# MCU023_MSP432E_GPIO_USB.net
KiCad netlist of a schematic drawn in Altium Designer
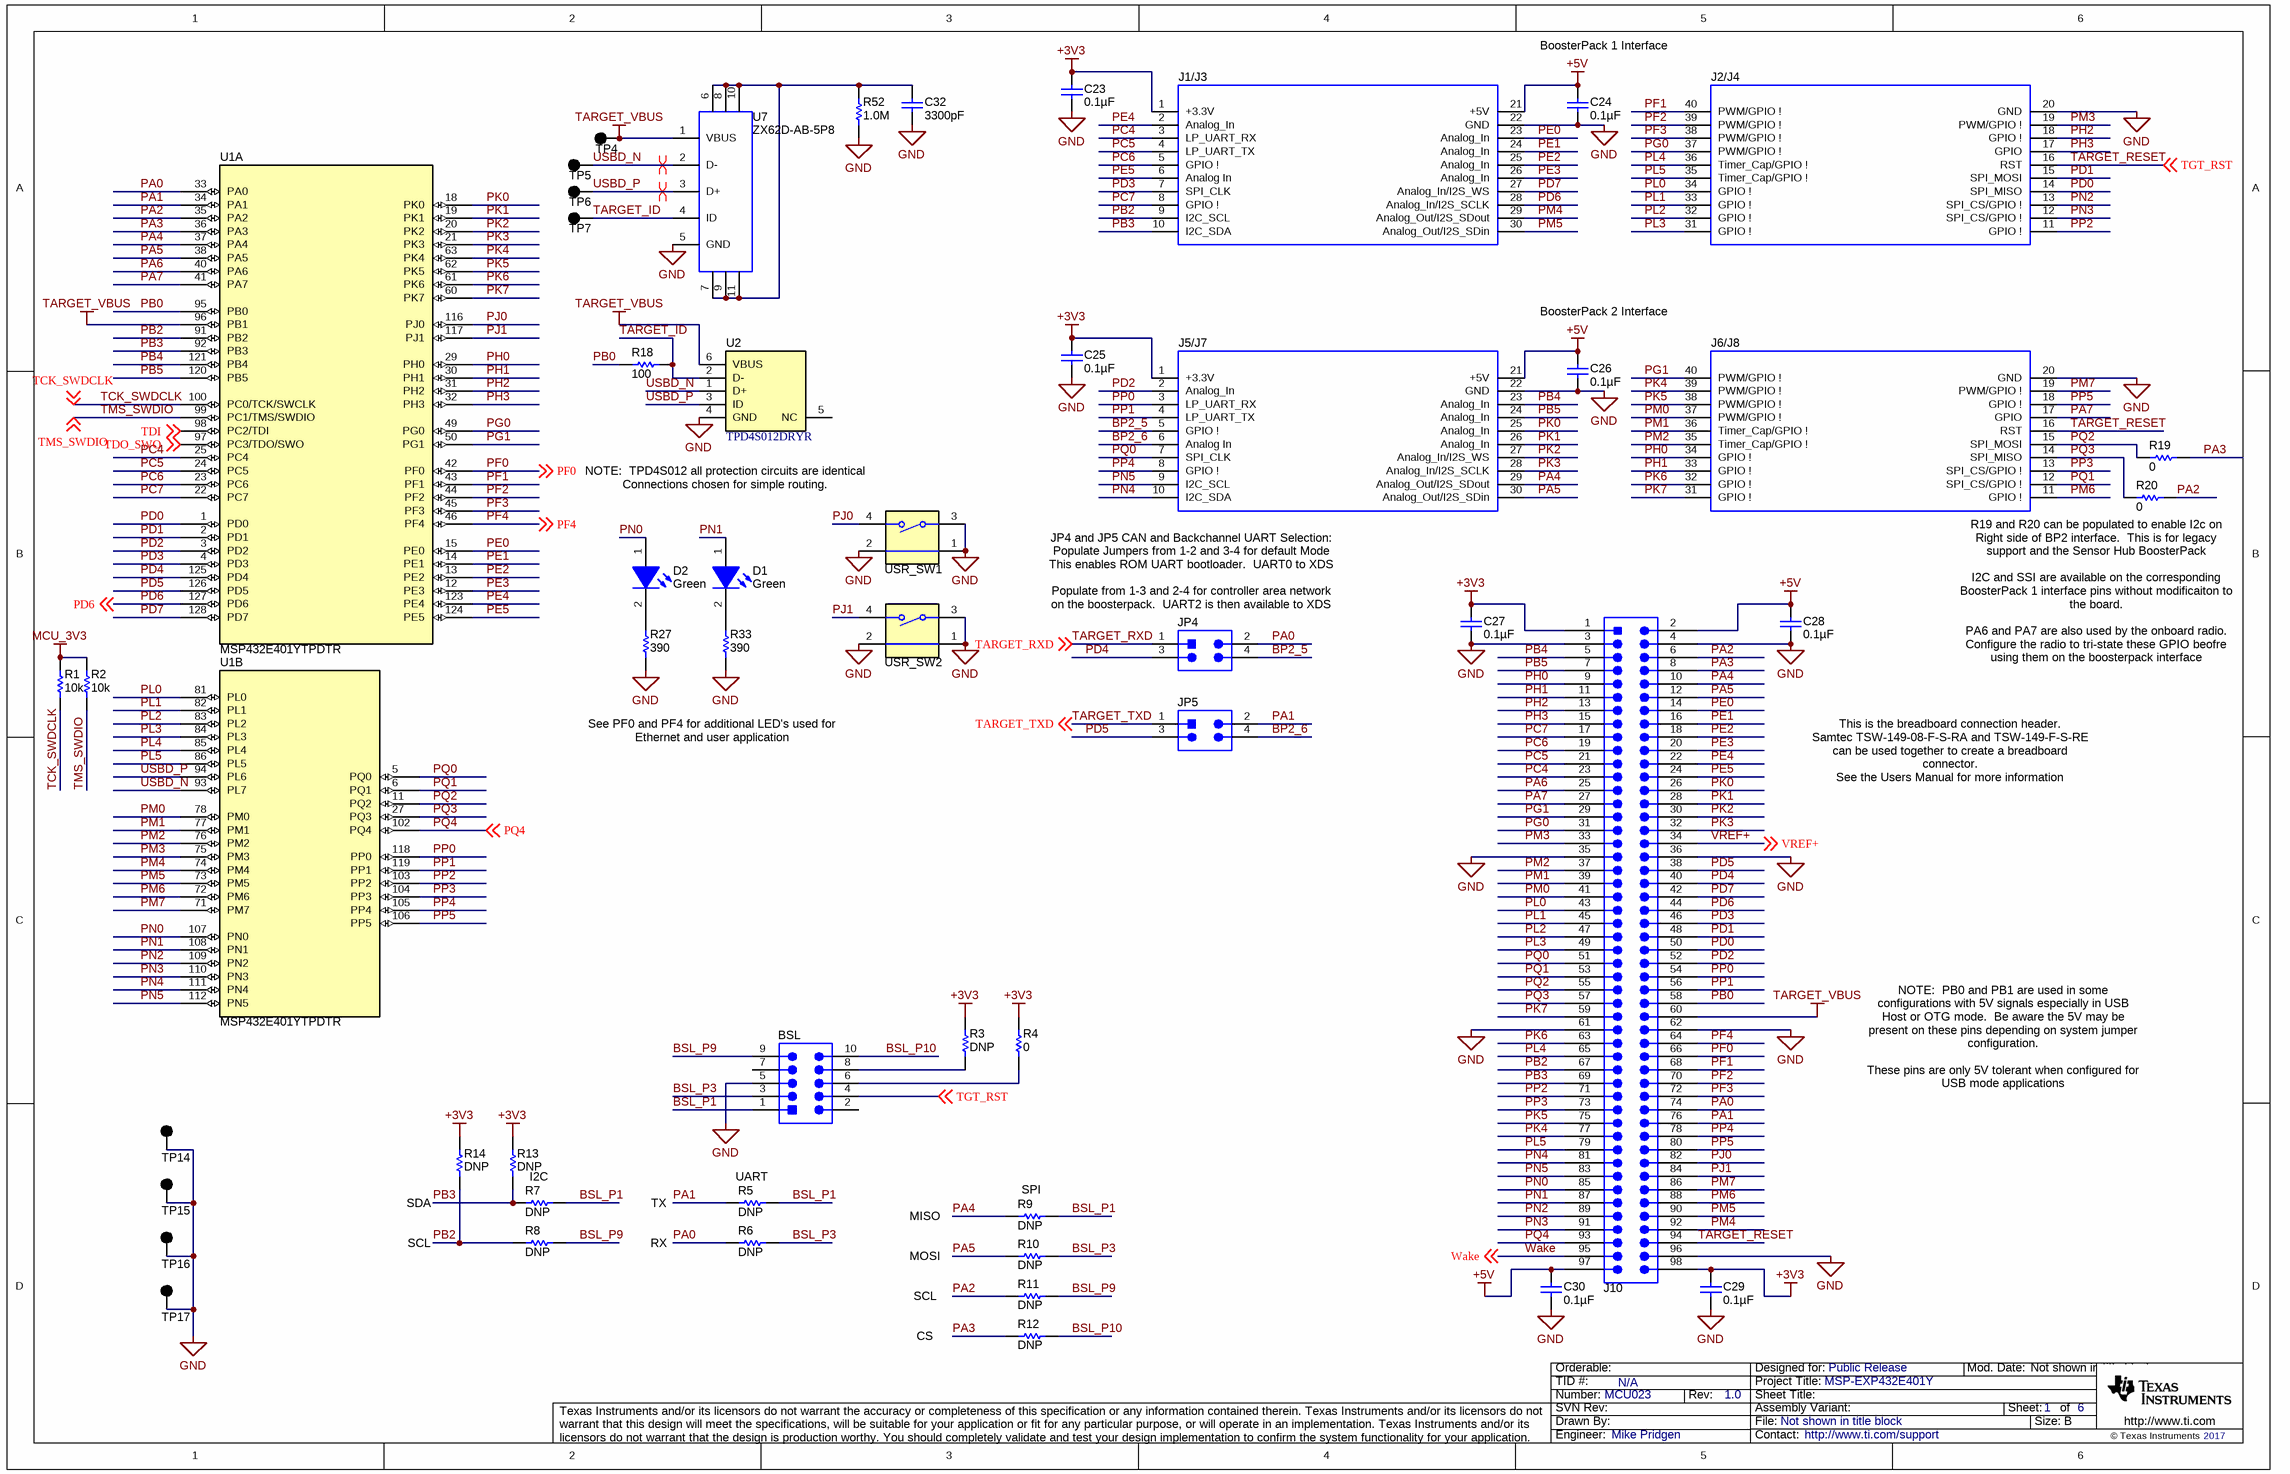
[diagram p0: MCU023_MSP432E_GPIO_USB.SchDoc]

(export (version "E")
  (design (tool "Eeschema 10.0.6"))
  (components
    (comp (ref "BSL")
      (value "AWHW-10G-0202-T")
      (footprint "Assman_AWHW-10G-0x02-T")
      (description "Header(Shrouded), 2.54mm, 5x2, Gold, TH")
      (fields
        (field (name "MANUFACTURER") "Assman WSW")
        (field (name "SYMBOLCREATOR") "a0412235")
        (field (name "PUBLISHER") "Texas Instruments")
      )
      (libsource (lib "Connectors_Other") (part "AWHW-10G-0202-T"))
    )
    (comp (ref "C23")
      (value "GRM155R71C104KA88D")
      (footprint "0402")
      (description "CAP, CERM, 0.1 µF, 16 V, +/- 10%, X7R, 0402")
      (fields
        (field (name "VALUEDISPLAYED") "0.1µF")
        (field (name "MANUFACTURER") "MuRata")
        (field (name "PUBLISHER") "Texas Instruments")
      )
      (libsource (lib "Capacitor_Ceramic") (part "GRM155R71C104KA88D"))
    )
    (comp (ref "C24")
      (value "GRM155R71C104KA88D")
      (footprint "0402")
      (description "CAP, CERM, 0.1 µF, 16 V, +/- 10%, X7R, 0402")
      (fields
        (field (name "VALUEDISPLAYED") "0.1µF")
        (field (name "MANUFACTURER") "MuRata")
        (field (name "PUBLISHER") "Texas Instruments")
      )
      (libsource (lib "Capacitor_Ceramic") (part "GRM155R71C104KA88D"))
    )
    (comp (ref "C25")
      (value "GRM155R71C104KA88D")
      (footprint "0402")
      (description "CAP, CERM, 0.1 µF, 16 V, +/- 10%, X7R, 0402")
      (fields
        (field (name "VALUEDISPLAYED") "0.1µF")
        (field (name "MANUFACTURER") "MuRata")
        (field (name "PUBLISHER") "Texas Instruments")
      )
      (libsource (lib "Capacitor_Ceramic") (part "GRM155R71C104KA88D"))
    )
    (comp (ref "C26")
      (value "GRM155R71C104KA88D")
      (footprint "0402")
      (description "CAP, CERM, 0.1 µF, 16 V, +/- 10%, X7R, 0402")
      (fields
        (field (name "VALUEDISPLAYED") "0.1µF")
        (field (name "MANUFACTURER") "MuRata")
        (field (name "PUBLISHER") "Texas Instruments")
      )
      (libsource (lib "Capacitor_Ceramic") (part "GRM155R71C104KA88D"))
    )
    (comp (ref "C27")
      (value "GRM155R71C104KA88D")
      (footprint "0402")
      (description "CAP, CERM, 0.1 µF, 16 V, +/- 10%, X7R, 0402")
      (fields
        (field (name "VALUEDISPLAYED") "0.1µF")
        (field (name "MANUFACTURER") "MuRata")
        (field (name "PUBLISHER") "Texas Instruments")
      )
      (libsource (lib "Capacitor_Ceramic") (part "GRM155R71C104KA88D"))
    )
    (comp (ref "C28")
      (value "GRM155R71C104KA88D")
      (footprint "0402")
      (description "CAP, CERM, 0.1 µF, 16 V, +/- 10%, X7R, 0402")
      (fields
        (field (name "VALUEDISPLAYED") "0.1µF")
        (field (name "MANUFACTURER") "MuRata")
        (field (name "PUBLISHER") "Texas Instruments")
      )
      (libsource (lib "Capacitor_Ceramic") (part "GRM155R71C104KA88D"))
    )
    (comp (ref "C29")
      (value "GRM155R71C104KA88D")
      (footprint "0402")
      (description "CAP, CERM, 0.1 µF, 16 V, +/- 10%, X7R, 0402")
      (fields
        (field (name "VALUEDISPLAYED") "0.1µF")
        (field (name "MANUFACTURER") "MuRata")
        (field (name "PUBLISHER") "Texas Instruments")
      )
      (libsource (lib "Capacitor_Ceramic") (part "GRM155R71C104KA88D"))
    )
    (comp (ref "C30")
      (value "GRM155R71C104KA88D")
      (footprint "0402")
      (description "CAP, CERM, 0.1 µF, 16 V, +/- 10%, X7R, 0402")
      (fields
        (field (name "VALUEDISPLAYED") "0.1µF")
        (field (name "MANUFACTURER") "MuRata")
        (field (name "PUBLISHER") "Texas Instruments")
      )
      (libsource (lib "Capacitor_Ceramic") (part "GRM155R71C104KA88D"))
    )
    (comp (ref "C32")
      (value "GRM188R71H332KA01D")
      (footprint "0603")
      (description "CAP, CERM, 3300 pF, 50 V, +/- 10%, X7R, 0603")
      (fields
        (field (name "VALUEDISPLAYED") "3300pF")
        (field (name "MANUFACTURER") "MuRata")
        (field (name "PUBLISHER") "Texas Instruments")
      )
      (libsource (lib "Capacitor_Ceramic") (part "GRM188R71H332KA01D"))
    )
    (comp (ref "D1")
      (value "Green")
      (footprint "LED_LTST-C190")
      (description "LED, Green, SMD")
      (fields
        (field (name "PARTNUMBER") "LTST-C190GKT")
        (field (name "MANUFACTURER") "Lite-On")
        (field (name "PUBLISHER") "Texas Instruments")
      )
      (libsource (lib "LED") (part "LTST-C190GKT"))
    )
    (comp (ref "D2")
      (value "Green")
      (footprint "LED_LTST-C190")
      (description "LED, Green, SMD")
      (fields
        (field (name "PARTNUMBER") "LTST-C190GKT")
        (field (name "MANUFACTURER") "Lite-On")
        (field (name "PUBLISHER") "Texas Instruments")
      )
      (libsource (lib "LED") (part "LTST-C190GKT"))
    )
    (comp (ref "J1/J3")
      (value "SSQ-110-03-T-D")
      (footprint "BoosterPack_40pin_J1J3")
      (description "Receptacle, 2.54mm, 10x2, Tin, TH")
      (fields
        (field (name "MANUFACTURER") "Samtec")
        (field (name "ALTERNATE PARTNUMBER") "CRD-081413-A-G")
        (field (name "SYMBOLCREATOR") "a0412235")
        (field (name "PUBLISHER") "Texas Instruments")
      )
      (libsource (lib "Hardware") (part "BoosterPack_40pin_J1J3"))
    )
    (comp (ref "J2/J4")
      (value "SSQ-110-03-T-D")
      (footprint "BoosterPack_40pin_J2J4")
      (description "Receptacle, 2.54mm, 10x2, Tin, TH")
      (fields
        (field (name "MANUFACTURER") "Samtec")
        (field (name "ALTERNATE PARTNUMBER") "CRD-081413-A-G")
        (field (name "SYMBOLCREATOR") "a0412235")
        (field (name "PUBLISHER") "Texas Instruments")
      )
      (libsource (lib "Hardware") (part "BoosterPack_40pin_J2J4"))
    )
    (comp (ref "J5/J7")
      (value "SSQ-110-03-T-D")
      (footprint "BoosterPack_40pin_J1J3")
      (description "Receptacle, 2.54mm, 10x2, Tin, TH")
      (fields
        (field (name "MANUFACTURER") "Samtec")
        (field (name "ALTERNATE PARTNUMBER") "CRD-081413-A-G")
        (field (name "SYMBOLCREATOR") "a0412235")
        (field (name "PUBLISHER") "Texas Instruments")
      )
      (libsource (lib "Hardware") (part "BoosterPack_40pin_J1J3"))
    )
    (comp (ref "J6/J8")
      (value "SSQ-110-03-T-D")
      (footprint "BoosterPack_40pin_J2J4")
      (description "Receptacle, 2.54mm, 10x2, Tin, TH")
      (fields
        (field (name "MANUFACTURER") "Samtec")
        (field (name "ALTERNATE PARTNUMBER") "CRD-081413-A-G")
        (field (name "SYMBOLCREATOR") "a0412235")
        (field (name "PUBLISHER") "Texas Instruments")
      )
      (libsource (lib "Hardware") (part "BoosterPack_40pin_J2J4"))
    )
    (comp (ref "J10")
      (value "TSW-149-07-S-D")
      (footprint "Samtec_TSW-149-07-x-D")
      (description "Header, 2.54mm, 49x2, Gold, TH")
      (fields
        (field (name "MANUFACTURER") "Samtec")
        (field (name "SYMBOLCREATOR") "Altium")
        (field (name "PUBLISHER") "Texas Instruments")
      )
      (libsource (lib "Connectors_Samtec1") (part "TSW-149-07-S-D"))
    )
    (comp (ref "JP4")
      (value "PBC02DAAN")
      (footprint "Sullins_PxC02DAAN")
      (description "Header, 2.54mm, 2x2, Gold, TH")
      (fields
        (field (name "MANUFACTURER") "Sullins Connector Solutions")
        (field (name "SYMBOLCREATOR") "a0412235")
        (field (name "PUBLISHER") "Texas Instruments")
      )
      (libsource (lib "Connectors_Sullins") (part "PBC02DAAN"))
    )
    (comp (ref "JP5")
      (value "PBC02DAAN")
      (footprint "Sullins_PxC02DAAN")
      (description "Header, 2.54mm, 2x2, Gold, TH")
      (fields
        (field (name "MANUFACTURER") "Sullins Connector Solutions")
        (field (name "SYMBOLCREATOR") "a0412235")
        (field (name "PUBLISHER") "Texas Instruments")
      )
      (libsource (lib "Connectors_Sullins") (part "PBC02DAAN"))
    )
    (comp (ref "R1")
      (value "CRCW040210K0JNED")
      (footprint "0402")
      (description "RES, 10 k, 5%, 0.063 W, 0402")
      (fields
        (field (name "VALUEDISPLAYED") "10k")
        (field (name "MANUFACTURER") "Vishay-Dale")
        (field (name "PUBLISHER") "Texas Instruments")
      )
      (libsource (lib "Resistor_0402") (part "CRCW040210K0JNED"))
    )
    (comp (ref "R2")
      (value "CRCW040210K0JNED")
      (footprint "0402")
      (description "RES, 10 k, 5%, 0.063 W, 0402")
      (fields
        (field (name "VALUEDISPLAYED") "10k")
        (field (name "MANUFACTURER") "Vishay-Dale")
        (field (name "PUBLISHER") "Texas Instruments")
      )
      (libsource (lib "Resistor_0402") (part "CRCW040210K0JNED"))
    )
    (comp (ref "R3")
      (value "ERJ-2GE0R00X")
      (footprint "0402")
      (description "RES, 0, 5%, 0.063 W, 0402")
      (fields
        (field (name "VALUEDISPLAYED") "DNP")
        (field (name "MANUFACTURER") "Panasonic")
        (field (name "PUBLISHER") "Texas Instruments")
      )
      (libsource (lib "Resistor_0402") (part "ERJ-2GE0R00X"))
    )
    (comp (ref "R4")
      (value "ERJ-2GE0R00X")
      (footprint "0402")
      (description "RES, 0, 5%, 0.063 W, 0402")
      (fields
        (field (name "VALUEDISPLAYED") "0")
        (field (name "MANUFACTURER") "Panasonic")
        (field (name "PUBLISHER") "Texas Instruments")
      )
      (libsource (lib "Resistor_0402") (part "ERJ-2GE0R00X"))
    )
    (comp (ref "R5")
      (value "ERJ-2GE0R00X")
      (footprint "0402")
      (description "RES, 0, 5%, 0.063 W, 0402")
      (fields
        (field (name "VALUEDISPLAYED") "DNP")
        (field (name "MANUFACTURER") "Panasonic")
        (field (name "PUBLISHER") "Texas Instruments")
      )
      (libsource (lib "Resistor_0402") (part "ERJ-2GE0R00X"))
    )
    (comp (ref "R6")
      (value "ERJ-2GE0R00X")
      (footprint "0402")
      (description "RES, 0, 5%, 0.063 W, 0402")
      (fields
        (field (name "VALUEDISPLAYED") "DNP")
        (field (name "MANUFACTURER") "Panasonic")
        (field (name "PUBLISHER") "Texas Instruments")
      )
      (libsource (lib "Resistor_0402") (part "ERJ-2GE0R00X"))
    )
    (comp (ref "R7")
      (value "ERJ-2GE0R00X")
      (footprint "0402")
      (description "RES, 0, 5%, 0.063 W, 0402")
      (fields
        (field (name "VALUEDISPLAYED") "DNP")
        (field (name "MANUFACTURER") "Panasonic")
        (field (name "PUBLISHER") "Texas Instruments")
      )
      (libsource (lib "Resistor_0402") (part "ERJ-2GE0R00X"))
    )
    (comp (ref "R8")
      (value "ERJ-2GE0R00X")
      (footprint "0402")
      (description "RES, 0, 5%, 0.063 W, 0402")
      (fields
        (field (name "VALUEDISPLAYED") "DNP")
        (field (name "MANUFACTURER") "Panasonic")
        (field (name "PUBLISHER") "Texas Instruments")
      )
      (libsource (lib "Resistor_0402") (part "ERJ-2GE0R00X"))
    )
    (comp (ref "R9")
      (value "ERJ-2GE0R00X")
      (footprint "0402")
      (description "RES, 0, 5%, 0.063 W, 0402")
      (fields
        (field (name "VALUEDISPLAYED") "DNP")
        (field (name "MANUFACTURER") "Panasonic")
        (field (name "PUBLISHER") "Texas Instruments")
      )
      (libsource (lib "Resistor_0402") (part "ERJ-2GE0R00X"))
    )
    (comp (ref "R10")
      (value "ERJ-2GE0R00X")
      (footprint "0402")
      (description "RES, 0, 5%, 0.063 W, 0402")
      (fields
        (field (name "VALUEDISPLAYED") "DNP")
        (field (name "MANUFACTURER") "Panasonic")
        (field (name "PUBLISHER") "Texas Instruments")
      )
      (libsource (lib "Resistor_0402") (part "ERJ-2GE0R00X"))
    )
    (comp (ref "R11")
      (value "ERJ-2GE0R00X")
      (footprint "0402")
      (description "RES, 0, 5%, 0.063 W, 0402")
      (fields
        (field (name "VALUEDISPLAYED") "DNP")
        (field (name "MANUFACTURER") "Panasonic")
        (field (name "PUBLISHER") "Texas Instruments")
      )
      (libsource (lib "Resistor_0402") (part "ERJ-2GE0R00X"))
    )
    (comp (ref "R12")
      (value "ERJ-2GE0R00X")
      (footprint "0402")
      (description "RES, 0, 5%, 0.063 W, 0402")
      (fields
        (field (name "VALUEDISPLAYED") "DNP")
        (field (name "MANUFACTURER") "Panasonic")
        (field (name "PUBLISHER") "Texas Instruments")
      )
      (libsource (lib "Resistor_0402") (part "ERJ-2GE0R00X"))
    )
    (comp (ref "R13")
      (value "CRCW04023K30JNED")
      (footprint "0402")
      (description "RES, 3.3 k, 5%, 0.063 W, 0402")
      (fields
        (field (name "VALUEDISPLAYED") "DNP")
        (field (name "MANUFACTURER") "Vishay-Dale")
        (field (name "PUBLISHER") "Texas Instruments")
      )
      (libsource (lib "Resistor_0402") (part "CRCW04023K30JNED"))
    )
    (comp (ref "R14")
      (value "CRCW04023K30JNED")
      (footprint "0402")
      (description "RES, 3.3 k, 5%, 0.063 W, 0402")
      (fields
        (field (name "VALUEDISPLAYED") "DNP")
        (field (name "MANUFACTURER") "Vishay-Dale")
        (field (name "PUBLISHER") "Texas Instruments")
      )
      (libsource (lib "Resistor_0402") (part "CRCW04023K30JNED"))
    )
    (comp (ref "R18")
      (value "CRCW0402100RJNED")
      (footprint "0402")
      (description "RES, 100, 5%, 0.063 W, 0402")
      (fields
        (field (name "VALUEDISPLAYED") "100")
        (field (name "MANUFACTURER") "Vishay-Dale")
        (field (name "PUBLISHER") "Texas Instruments")
      )
      (libsource (lib "Resistor_0402") (part "CRCW0402100RJNED"))
    )
    (comp (ref "R19")
      (value "ERJ-2GE0R00X")
      (footprint "0402")
      (description "RES, 0, 5%, 0.063 W, 0402")
      (fields
        (field (name "VALUEDISPLAYED") "0")
        (field (name "MANUFACTURER") "Panasonic")
        (field (name "PUBLISHER") "Texas Instruments")
      )
      (libsource (lib "Resistor_0402") (part "ERJ-2GE0R00X"))
    )
    (comp (ref "R20")
      (value "ERJ-2GE0R00X")
      (footprint "0402")
      (description "RES, 0, 5%, 0.063 W, 0402")
      (fields
        (field (name "VALUEDISPLAYED") "0")
        (field (name "MANUFACTURER") "Panasonic")
        (field (name "PUBLISHER") "Texas Instruments")
      )
      (libsource (lib "Resistor_0402") (part "ERJ-2GE0R00X"))
    )
    (comp (ref "R27")
      (value "CRCW0402390RJNED")
      (footprint "0402")
      (description "RES, 390, 5%, 0.063 W, 0402")
      (fields
        (field (name "VALUEDISPLAYED") "390")
        (field (name "MANUFACTURER") "Vishay-Dale")
        (field (name "PUBLISHER") "Texas Instruments")
      )
      (libsource (lib "Resistor_0402") (part "CRCW0402390RJNED"))
    )
    (comp (ref "R33")
      (value "CRCW0402390RJNED")
      (footprint "0402")
      (description "RES, 390, 5%, 0.063 W, 0402")
      (fields
        (field (name "VALUEDISPLAYED") "390")
        (field (name "MANUFACTURER") "Vishay-Dale")
        (field (name "PUBLISHER") "Texas Instruments")
      )
      (libsource (lib "Resistor_0402") (part "CRCW0402390RJNED"))
    )
    (comp (ref "R52")
      (value "CRCW06031M00JNEA")
      (footprint "0603")
      (description "RES, 1.0 M, 5%, 0.1 W, 0603")
      (fields
        (field (name "VALUEDISPLAYED") "1.0M")
        (field (name "MANUFACTURER") "Vishay-Dale")
        (field (name "PUBLISHER") "Texas Instruments")
      )
      (libsource (lib "Resistor_0603") (part "CRCW06031M00JNEA"))
    )
    (comp (ref "TP4")
      (value "5001")
      (footprint "Keystone5001")
      (description "Test Point, Miniature, Black, TH")
      (fields (field (name "MANUFACTURER") "Keystone") (field (name "PUBLISHER") "Texas Instruments"))
      (libsource (lib "Connectors_Keystone") (part "5001"))
    )
    (comp (ref "TP5")
      (value "5001")
      (footprint "Keystone5001")
      (description "Test Point, Miniature, Black, TH")
      (fields (field (name "MANUFACTURER") "Keystone") (field (name "PUBLISHER") "Texas Instruments"))
      (libsource (lib "Connectors_Keystone") (part "5001"))
    )
    (comp (ref "TP6")
      (value "5001")
      (footprint "Keystone5001")
      (description "Test Point, Miniature, Black, TH")
      (fields (field (name "MANUFACTURER") "Keystone") (field (name "PUBLISHER") "Texas Instruments"))
      (libsource (lib "Connectors_Keystone") (part "5001"))
    )
    (comp (ref "TP7")
      (value "5001")
      (footprint "Keystone5001")
      (description "Test Point, Miniature, Black, TH")
      (fields (field (name "MANUFACTURER") "Keystone") (field (name "PUBLISHER") "Texas Instruments"))
      (libsource (lib "Connectors_Keystone") (part "5001"))
    )
    (comp (ref "TP14")
      (value "5001")
      (footprint "Keystone5001")
      (description "Test Point, Miniature, Black, TH")
      (fields (field (name "MANUFACTURER") "Keystone") (field (name "PUBLISHER") "Texas Instruments"))
      (libsource (lib "Connectors_Keystone") (part "5001"))
    )
    (comp (ref "TP15")
      (value "5001")
      (footprint "Keystone5001")
      (description "Test Point, Miniature, Black, TH")
      (fields (field (name "MANUFACTURER") "Keystone") (field (name "PUBLISHER") "Texas Instruments"))
      (libsource (lib "Connectors_Keystone") (part "5001"))
    )
    (comp (ref "TP16")
      (value "5001")
      (footprint "Keystone5001")
      (description "Test Point, Miniature, Black, TH")
      (fields (field (name "MANUFACTURER") "Keystone") (field (name "PUBLISHER") "Texas Instruments"))
      (libsource (lib "Connectors_Keystone") (part "5001"))
    )
    (comp (ref "TP17")
      (value "5001")
      (footprint "Keystone5001")
      (description "Test Point, Miniature, Black, TH")
      (fields (field (name "MANUFACTURER") "Keystone") (field (name "PUBLISHER") "Texas Instruments"))
      (libsource (lib "Connectors_Keystone") (part "5001"))
    )
    (comp (ref "U1")
      (value "MSP432E401YTPDTR")
      (footprint "PDT0128A")
      (description "IoT enabled High performance 32-bit ARM(R) Cortex(R)-M4F based MCU, PDT0128A (TQFP-128)")
      (fields
        (field (name "MANUFACTURER") "Texas Instruments")
        (field (name "SYMBOLCREATOR") "a0411947")
        (field (name "PUBLISHER") "Texas Instruments")
      )
      (libsource (lib "TI_Pre_Release") (part "TM4C1294NCPDTI3R"))
    )
    (comp (ref "U2")
      (value "TPD4S012DRYR")
      (footprint "DRY0006A")
      (fields
        (field (name "MANUFACTURER") "Texas Instruments")
        (field (name "ALTERNATE PARTNUMBER") "Equivalent")
      )
      (libsource (lib "TI Interface ESD EMI Protection") (part "TPD4S012DRYR"))
    )
    (comp (ref "U7")
      (value "ZX62D-AB-5P8")
      (footprint "Hirose-ZX62D-AB-5P8")
      (description "Connector, Receptacle, Micro-USB Type AB, R/A, Bottom Mount SMT")
      (fields
        (field (name "MANUFACTURER") "Hirose Electric Co. Ltd.")
        (field (name "SYMBOLCREATOR") "a0411947")
        (field (name "PUBLISHER") "Texas Instruments")
      )
      (libsource (lib "Connectors_Other") (part "ZX62D-AB-5P8"))
    )
    (comp (ref "USR_SW1")
      (value "1188E-1K2-V-TR")
      (footprint "SW_1188E")
      (description "Switch, SPST, 0.05 A, 12 VDC, SMD")
      (fields
        (field (name "MANUFACTURER") "Diptronics")
        (field (name "SYMBOLCREATOR") "Altium")
        (field (name "PUBLISHER") "Texas Instruments")
      )
      (libsource (lib "Switches") (part "1188E-1K2-V-TR"))
    )
    (comp (ref "USR_SW2")
      (value "1188E-1K2-V-TR")
      (footprint "SW_1188E")
      (description "Switch, SPST, 0.05 A, 12 VDC, SMD")
      (fields
        (field (name "MANUFACTURER") "Diptronics")
        (field (name "SYMBOLCREATOR") "Altium")
        (field (name "PUBLISHER") "Texas Instruments")
      )
      (libsource (lib "Switches") (part "1188E-1K2-V-TR"))
    )
  )
  (nets
    (net (code "1") (name "+3V3") (class "Default")
      (node (ref "C23") (pin "2") (pinfunction "2_2") (pintype "passive"))
      (node (ref "C25") (pin "2") (pinfunction "2_2") (pintype "passive"))
      (node (ref "C27") (pin "2") (pinfunction "2_2") (pintype "passive"))
      (node (ref "C29") (pin "2") (pinfunction "2_2") (pintype "passive"))
      (node (ref "J1/J3") (pin "1") (pinfunction "+3.3V_1") (pintype "power_in"))
      (node (ref "J10") (pin "1") (pinfunction "1_1") (pintype "passive"))
      (node (ref "J10") (pin "98") (pinfunction "98_98") (pintype "passive"))
      (node (ref "J5/J7") (pin "1") (pinfunction "+3.3V_1") (pintype "power_in"))
      (node (ref "R13") (pin "2") (pinfunction "2_2") (pintype "passive"))
      (node (ref "R14") (pin "2") (pinfunction "2_2") (pintype "passive"))
      (node (ref "R3") (pin "2") (pinfunction "2_2") (pintype "passive"))
      (node (ref "R4") (pin "2") (pinfunction "2_2") (pintype "passive"))
    )
    (net (code "2") (name "+5V") (class "Default")
      (node (ref "C24") (pin "2") (pinfunction "2_2") (pintype "passive"))
      (node (ref "C26") (pin "2") (pinfunction "2_2") (pintype "passive"))
      (node (ref "C28") (pin "2") (pinfunction "2_2") (pintype "passive"))
      (node (ref "C30") (pin "2") (pinfunction "2_2") (pintype "passive"))
      (node (ref "J1/J3") (pin "21") (pinfunction "+5V_21") (pintype "power_in"))
      (node (ref "J10") (pin "2") (pinfunction "2_2") (pintype "passive"))
      (node (ref "J10") (pin "97") (pinfunction "97_97") (pintype "passive"))
      (node (ref "J5/J7") (pin "21") (pinfunction "+5V_21") (pintype "power_in"))
    )
    (net (code "3") (name "/BP2_5") (class "Default")
      (node (ref "J5/J7") (pin "5") (pinfunction "GPIO_!_5") (pintype "passive"))
      (node (ref "JP4") (pin "4") (pinfunction "4_4") (pintype "passive"))
    )
    (net (code "4") (name "/BP2_6") (class "Default")
      (node (ref "J5/J7") (pin "6") (pinfunction "Analog_In_6") (pintype "passive"))
      (node (ref "JP5") (pin "4") (pinfunction "4_4") (pintype "passive"))
    )
    (net (code "5") (name "/BSL_P1") (class "Default")
      (node (ref "BSL") (pin "1") (pinfunction "1_1") (pintype "passive"))
      (node (ref "R5") (pin "1") (pinfunction "1_1") (pintype "passive"))
      (node (ref "R7") (pin "1") (pinfunction "1_1") (pintype "passive"))
      (node (ref "R9") (pin "1") (pinfunction "1_1") (pintype "passive"))
    )
    (net (code "6") (name "/BSL_P3") (class "Default")
      (node (ref "BSL") (pin "3") (pinfunction "3_3") (pintype "passive"))
      (node (ref "R10") (pin "1") (pinfunction "1_1") (pintype "passive"))
      (node (ref "R6") (pin "1") (pinfunction "1_1") (pintype "passive"))
    )
    (net (code "7") (name "/BSL_P9") (class "Default")
      (node (ref "BSL") (pin "9") (pinfunction "9_9") (pintype "passive"))
      (node (ref "R11") (pin "1") (pinfunction "1_1") (pintype "passive"))
      (node (ref "R8") (pin "1") (pinfunction "1_1") (pintype "passive"))
    )
    (net (code "8") (name "/BSL_P10") (class "Default")
      (node (ref "BSL") (pin "10") (pinfunction "10_10") (pintype "passive"))
      (node (ref "R12") (pin "1") (pinfunction "1_1") (pintype "passive"))
    )
    (net (code "9") (name "/PA0") (class "Default")
      (node (ref "J10") (pin "74") (pinfunction "74_74") (pintype "passive"))
      (node (ref "JP4") (pin "2") (pinfunction "2_2") (pintype "passive"))
      (node (ref "R6") (pin "2") (pinfunction "2_2") (pintype "passive"))
      (node (ref "U1") (pin "33") (pinfunction "PA0_33") (pintype "bidirectional"))
    )
    (net (code "10") (name "/PA1") (class "Default")
      (node (ref "J10") (pin "76") (pinfunction "76_76") (pintype "passive"))
      (node (ref "JP5") (pin "2") (pinfunction "2_2") (pintype "passive"))
      (node (ref "R5") (pin "2") (pinfunction "2_2") (pintype "passive"))
      (node (ref "U1") (pin "34") (pinfunction "PA1_34") (pintype "bidirectional"))
    )
    (net (code "11") (name "/PA2") (class "Default")
      (node (ref "J10") (pin "6") (pinfunction "6_6") (pintype "passive"))
      (node (ref "R11") (pin "2") (pinfunction "2_2") (pintype "passive"))
      (node (ref "R20") (pin "2") (pinfunction "2_2") (pintype "passive"))
      (node (ref "U1") (pin "35") (pinfunction "PA2_35") (pintype "bidirectional"))
    )
    (net (code "12") (name "/PA3") (class "Default")
      (node (ref "J10") (pin "8") (pinfunction "8_8") (pintype "passive"))
      (node (ref "R12") (pin "2") (pinfunction "2_2") (pintype "passive"))
      (node (ref "R19") (pin "2") (pinfunction "2_2") (pintype "passive"))
      (node (ref "U1") (pin "36") (pinfunction "PA3_36") (pintype "bidirectional"))
    )
    (net (code "13") (name "/PA4") (class "Default")
      (node (ref "J10") (pin "10") (pinfunction "10_10") (pintype "passive"))
      (node (ref "J5/J7") (pin "29") (pinfunction "Analog_Out/I2S_SDout_29") (pintype "passive"))
      (node (ref "R9") (pin "2") (pinfunction "2_2") (pintype "passive"))
      (node (ref "U1") (pin "37") (pinfunction "PA4_37") (pintype "bidirectional"))
    )
    (net (code "14") (name "/PA5") (class "Default")
      (node (ref "J10") (pin "12") (pinfunction "12_12") (pintype "passive"))
      (node (ref "J5/J7") (pin "30") (pinfunction "Analog_Out/I2S_SDin_30") (pintype "passive"))
      (node (ref "R10") (pin "2") (pinfunction "2_2") (pintype "passive"))
      (node (ref "U1") (pin "38") (pinfunction "PA5_38") (pintype "bidirectional"))
    )
    (net (code "15") (name "/PA6") (class "Default")
      (node (ref "J10") (pin "25") (pinfunction "25_25") (pintype "passive"))
      (node (ref "U1") (pin "40") (pinfunction "PA6_40") (pintype "bidirectional"))
    )
    (net (code "16") (name "/PA7") (class "Default")
      (node (ref "J10") (pin "27") (pinfunction "27_27") (pintype "passive"))
      (node (ref "J6/J8") (pin "17") (pinfunction "GPIO_17") (pintype "passive"))
      (node (ref "U1") (pin "41") (pinfunction "PA7_41") (pintype "bidirectional"))
    )
    (net (code "17") (name "/PB0") (class "Default")
      (node (ref "J10") (pin "58") (pinfunction "58_58") (pintype "passive"))
      (node (ref "R18") (pin "1") (pinfunction "1_1") (pintype "passive"))
      (node (ref "U1") (pin "95") (pinfunction "PB0_95") (pintype "bidirectional"))
    )
    (net (code "18") (name "/PB2") (class "Default")
      (node (ref "J1/J3") (pin "9") (pinfunction "I2C_SCL_9") (pintype "passive"))
      (node (ref "J10") (pin "67") (pinfunction "67_67") (pintype "passive"))
      (node (ref "R14") (pin "1") (pinfunction "1_1") (pintype "passive"))
      (node (ref "R8") (pin "2") (pinfunction "2_2") (pintype "passive"))
      (node (ref "U1") (pin "91") (pinfunction "PB2_91") (pintype "bidirectional"))
    )
    (net (code "19") (name "/PB3") (class "Default")
      (node (ref "J1/J3") (pin "10") (pinfunction "I2C_SDA_10") (pintype "passive"))
      (node (ref "J10") (pin "69") (pinfunction "69_69") (pintype "passive"))
      (node (ref "R13") (pin "1") (pinfunction "1_1") (pintype "passive"))
      (node (ref "R7") (pin "2") (pinfunction "2_2") (pintype "passive"))
      (node (ref "U1") (pin "92") (pinfunction "PB3_92") (pintype "bidirectional"))
    )
    (net (code "20") (name "/PB4") (class "Default")
      (node (ref "J10") (pin "5") (pinfunction "5_5") (pintype "passive"))
      (node (ref "J5/J7") (pin "23") (pinfunction "Analog_In_23") (pintype "passive"))
      (node (ref "U1") (pin "121") (pinfunction "PB4_121") (pintype "bidirectional"))
    )
    (net (code "21") (name "/PB5") (class "Default")
      (node (ref "J10") (pin "7") (pinfunction "7_7") (pintype "passive"))
      (node (ref "J5/J7") (pin "24") (pinfunction "Analog_In_24") (pintype "passive"))
      (node (ref "U1") (pin "120") (pinfunction "PB5_120") (pintype "bidirectional"))
    )
    (net (code "22") (name "/PC4") (class "Default")
      (node (ref "J1/J3") (pin "3") (pinfunction "LP_UART_RX_3") (pintype "passive"))
      (node (ref "J10") (pin "23") (pinfunction "23_23") (pintype "passive"))
      (node (ref "U1") (pin "25") (pinfunction "PC4_25") (pintype "bidirectional"))
    )
    (net (code "23") (name "/PC5") (class "Default")
      (node (ref "J1/J3") (pin "4") (pinfunction "LP_UART_TX_4") (pintype "passive"))
      (node (ref "J10") (pin "21") (pinfunction "21_21") (pintype "passive"))
      (node (ref "U1") (pin "24") (pinfunction "PC5_24") (pintype "bidirectional"))
    )
    (net (code "24") (name "/PC6") (class "Default")
      (node (ref "J1/J3") (pin "5") (pinfunction "GPIO_!_5") (pintype "passive"))
      (node (ref "J10") (pin "19") (pinfunction "19_19") (pintype "passive"))
      (node (ref "U1") (pin "23") (pinfunction "PC6_23") (pintype "bidirectional"))
    )
    (net (code "25") (name "/PC7") (class "Default")
      (node (ref "J1/J3") (pin "8") (pinfunction "GPIO_!_8") (pintype "passive"))
      (node (ref "J10") (pin "17") (pinfunction "17_17") (pintype "passive"))
      (node (ref "U1") (pin "22") (pinfunction "PC7_22") (pintype "bidirectional"))
    )
    (net (code "26") (name "/PD0") (class "Default")
      (node (ref "J10") (pin "50") (pinfunction "50_50") (pintype "passive"))
      (node (ref "J2/J4") (pin "14") (pinfunction "SPI_MISO_14") (pintype "passive"))
      (node (ref "U1") (pin "1") (pinfunction "PD0_1") (pintype "bidirectional"))
    )
    (net (code "27") (name "/PD1") (class "Default")
      (node (ref "J10") (pin "48") (pinfunction "48_48") (pintype "passive"))
      (node (ref "J2/J4") (pin "15") (pinfunction "SPI_MOSI_15") (pintype "passive"))
      (node (ref "U1") (pin "2") (pinfunction "PD1_2") (pintype "bidirectional"))
    )
    (net (code "28") (name "/PD2") (class "Default")
      (node (ref "J10") (pin "52") (pinfunction "52_52") (pintype "passive"))
      (node (ref "J5/J7") (pin "2") (pinfunction "Analog_In_2") (pintype "passive"))
      (node (ref "U1") (pin "3") (pinfunction "PD2_3") (pintype "bidirectional"))
    )
    (net (code "29") (name "/PD3") (class "Default")
      (node (ref "J1/J3") (pin "7") (pinfunction "SPI_CLK_7") (pintype "passive"))
      (node (ref "J10") (pin "46") (pinfunction "46_46") (pintype "passive"))
      (node (ref "U1") (pin "4") (pinfunction "PD3_4") (pintype "bidirectional"))
    )
    (net (code "30") (name "/PD4") (class "Default")
      (node (ref "J10") (pin "40") (pinfunction "40_40") (pintype "passive"))
      (node (ref "JP4") (pin "3") (pinfunction "3_3") (pintype "passive"))
      (node (ref "U1") (pin "125") (pinfunction "PD4_125") (pintype "bidirectional"))
    )
    (net (code "31") (name "/PD5") (class "Default")
      (node (ref "J10") (pin "38") (pinfunction "38_38") (pintype "passive"))
      (node (ref "JP5") (pin "3") (pinfunction "3_3") (pintype "passive"))
      (node (ref "U1") (pin "126") (pinfunction "PD5_126") (pintype "bidirectional"))
    )
    (net (code "32") (name "/PD7") (class "Default")
      (node (ref "J1/J3") (pin "27") (pinfunction "Analog_In/I2S_WS_27") (pintype "passive"))
      (node (ref "J10") (pin "42") (pinfunction "42_42") (pintype "passive"))
      (node (ref "U1") (pin "128") (pinfunction "PD7_128") (pintype "bidirectional"))
    )
    (net (code "33") (name "/PE0") (class "Default")
      (node (ref "J1/J3") (pin "23") (pinfunction "Analog_In_23") (pintype "passive"))
      (node (ref "J10") (pin "14") (pinfunction "14_14") (pintype "passive"))
      (node (ref "U1") (pin "15") (pinfunction "PE0_15") (pintype "bidirectional"))
    )
    (net (code "34") (name "/PE1") (class "Default")
      (node (ref "J1/J3") (pin "24") (pinfunction "Analog_In_24") (pintype "passive"))
      (node (ref "J10") (pin "16") (pinfunction "16_16") (pintype "passive"))
      (node (ref "U1") (pin "14") (pinfunction "PE1_14") (pintype "bidirectional"))
    )
    (net (code "35") (name "/PE2") (class "Default")
      (node (ref "J1/J3") (pin "25") (pinfunction "Analog_In_25") (pintype "passive"))
      (node (ref "J10") (pin "18") (pinfunction "18_18") (pintype "passive"))
      (node (ref "U1") (pin "13") (pinfunction "PE2_13") (pintype "bidirectional"))
    )
    (net (code "36") (name "/PE3") (class "Default")
      (node (ref "J1/J3") (pin "26") (pinfunction "Analog_In_26") (pintype "passive"))
      (node (ref "J10") (pin "20") (pinfunction "20_20") (pintype "passive"))
      (node (ref "U1") (pin "12") (pinfunction "PE3_12") (pintype "bidirectional"))
    )
    (net (code "37") (name "/PE4") (class "Default")
      (node (ref "J1/J3") (pin "2") (pinfunction "Analog_In_2") (pintype "passive"))
      (node (ref "J10") (pin "22") (pinfunction "22_22") (pintype "passive"))
      (node (ref "U1") (pin "123") (pinfunction "PE4_123") (pintype "bidirectional"))
    )
    (net (code "38") (name "/PE5") (class "Default")
      (node (ref "J1/J3") (pin "6") (pinfunction "Analog_In_6") (pintype "passive"))
      (node (ref "J10") (pin "24") (pinfunction "24_24") (pintype "passive"))
      (node (ref "U1") (pin "124") (pinfunction "PE5_124") (pintype "bidirectional"))
    )
    (net (code "39") (name "/PF1") (class "Default")
      (node (ref "J10") (pin "68") (pinfunction "68_68") (pintype "passive"))
      (node (ref "J2/J4") (pin "40") (pinfunction "PWM/GPIO_!_40") (pintype "passive"))
      (node (ref "U1") (pin "43") (pinfunction "PF1_43") (pintype "bidirectional"))
    )
    (net (code "40") (name "/PF2") (class "Default")
      (node (ref "J10") (pin "70") (pinfunction "70_70") (pintype "passive"))
      (node (ref "J2/J4") (pin "39") (pinfunction "PWM/GPIO_!_39") (pintype "passive"))
      (node (ref "U1") (pin "44") (pinfunction "PF2_44") (pintype "bidirectional"))
    )
    (net (code "41") (name "/PF3") (class "Default")
      (node (ref "J10") (pin "72") (pinfunction "72_72") (pintype "passive"))
      (node (ref "J2/J4") (pin "38") (pinfunction "PWM/GPIO_!_38") (pintype "passive"))
      (node (ref "U1") (pin "45") (pinfunction "PF3_45") (pintype "bidirectional"))
    )
    (net (code "42") (name "/PG0") (class "Default")
      (node (ref "J10") (pin "31") (pinfunction "31_31") (pintype "passive"))
      (node (ref "J2/J4") (pin "37") (pinfunction "PWM/GPIO_!_37") (pintype "passive"))
      (node (ref "U1") (pin "49") (pinfunction "PG0_49") (pintype "bidirectional"))
    )
    (net (code "43") (name "/PG1") (class "Default")
      (node (ref "J10") (pin "29") (pinfunction "29_29") (pintype "passive"))
      (node (ref "J6/J8") (pin "40") (pinfunction "PWM/GPIO_!_40") (pintype "passive"))
      (node (ref "U1") (pin "50") (pinfunction "PG1_50") (pintype "bidirectional"))
    )
    (net (code "44") (name "/PH0") (class "Default")
      (node (ref "J10") (pin "9") (pinfunction "9_9") (pintype "passive"))
      (node (ref "J6/J8") (pin "34") (pinfunction "GPIO_!_34") (pintype "passive"))
      (node (ref "U1") (pin "29") (pinfunction "PH0_29") (pintype "bidirectional"))
    )
    (net (code "45") (name "/PH1") (class "Default")
      (node (ref "J10") (pin "11") (pinfunction "11_11") (pintype "passive"))
      (node (ref "J6/J8") (pin "33") (pinfunction "GPIO_!_33") (pintype "passive"))
      (node (ref "U1") (pin "30") (pinfunction "PH1_30") (pintype "bidirectional"))
    )
    (net (code "46") (name "/PH2") (class "Default")
      (node (ref "J10") (pin "13") (pinfunction "13_13") (pintype "passive"))
      (node (ref "J2/J4") (pin "18") (pinfunction "GPIO_!_18") (pintype "passive"))
      (node (ref "U1") (pin "31") (pinfunction "PH2_31") (pintype "bidirectional"))
    )
    (net (code "47") (name "/PH3") (class "Default")
      (node (ref "J10") (pin "15") (pinfunction "15_15") (pintype "passive"))
      (node (ref "J2/J4") (pin "17") (pinfunction "GPIO_17") (pintype "passive"))
      (node (ref "U1") (pin "32") (pinfunction "PH3_32") (pintype "bidirectional"))
    )
    (net (code "48") (name "/PJ0") (class "Default")
      (node (ref "J10") (pin "82") (pinfunction "82_82") (pintype "passive"))
      (node (ref "U1") (pin "116") (pinfunction "PJ0_116") (pintype "bidirectional"))
      (node (ref "USR_SW1") (pin "4") (pinfunction "4_4") (pintype "passive"))
    )
    (net (code "49") (name "/PJ1") (class "Default")
      (node (ref "J10") (pin "84") (pinfunction "84_84") (pintype "passive"))
      (node (ref "U1") (pin "117") (pinfunction "PJ1_117") (pintype "bidirectional"))
      (node (ref "USR_SW2") (pin "4") (pinfunction "4_4") (pintype "passive"))
    )
    (net (code "50") (name "/PK0") (class "Default")
      (node (ref "J10") (pin "26") (pinfunction "26_26") (pintype "passive"))
      (node (ref "J5/J7") (pin "25") (pinfunction "Analog_In_25") (pintype "passive"))
      (node (ref "U1") (pin "18") (pinfunction "PK0_18") (pintype "bidirectional"))
    )
    (net (code "51") (name "/PK1") (class "Default")
      (node (ref "J10") (pin "28") (pinfunction "28_28") (pintype "passive"))
      (node (ref "J5/J7") (pin "26") (pinfunction "Analog_In_26") (pintype "passive"))
      (node (ref "U1") (pin "19") (pinfunction "PK1_19") (pintype "bidirectional"))
    )
    (net (code "52") (name "/PK2") (class "Default")
      (node (ref "J10") (pin "30") (pinfunction "30_30") (pintype "passive"))
      (node (ref "J5/J7") (pin "27") (pinfunction "Analog_In/I2S_WS_27") (pintype "passive"))
      (node (ref "U1") (pin "20") (pinfunction "PK2_20") (pintype "bidirectional"))
    )
    (net (code "53") (name "/PK3") (class "Default")
      (node (ref "J10") (pin "32") (pinfunction "32_32") (pintype "passive"))
      (node (ref "J5/J7") (pin "28") (pinfunction "Analog_In/I2S_SCLK_28") (pintype "passive"))
      (node (ref "U1") (pin "21") (pinfunction "PK3_21") (pintype "bidirectional"))
    )
    (net (code "54") (name "/PK4") (class "Default")
      (node (ref "J10") (pin "77") (pinfunction "77_77") (pintype "passive"))
      (node (ref "J6/J8") (pin "39") (pinfunction "PWM/GPIO_!_39") (pintype "passive"))
      (node (ref "U1") (pin "63") (pinfunction "PK4_63") (pintype "bidirectional"))
    )
    (net (code "55") (name "/PK5") (class "Default")
      (node (ref "J10") (pin "75") (pinfunction "75_75") (pintype "passive"))
      (node (ref "J6/J8") (pin "38") (pinfunction "PWM/GPIO_!_38") (pintype "passive"))
      (node (ref "U1") (pin "62") (pinfunction "PK5_62") (pintype "bidirectional"))
    )
    (net (code "56") (name "/PK6") (class "Default")
      (node (ref "J10") (pin "63") (pinfunction "63_63") (pintype "passive"))
      (node (ref "J6/J8") (pin "32") (pinfunction "GPIO_!_32") (pintype "passive"))
      (node (ref "U1") (pin "61") (pinfunction "PK6_61") (pintype "bidirectional"))
    )
    (net (code "57") (name "/PK7") (class "Default")
      (node (ref "J10") (pin "59") (pinfunction "59_59") (pintype "passive"))
      (node (ref "J6/J8") (pin "31") (pinfunction "GPIO_!_31") (pintype "passive"))
      (node (ref "U1") (pin "60") (pinfunction "PK7_60") (pintype "bidirectional"))
    )
    (net (code "58") (name "/PL0") (class "Default")
      (node (ref "J10") (pin "43") (pinfunction "43_43") (pintype "passive"))
      (node (ref "J2/J4") (pin "34") (pinfunction "GPIO_!_34") (pintype "passive"))
      (node (ref "U1") (pin "81") (pinfunction "PL0_81") (pintype "bidirectional"))
    )
    (net (code "59") (name "/PL1") (class "Default")
      (node (ref "J10") (pin "45") (pinfunction "45_45") (pintype "passive"))
      (node (ref "J2/J4") (pin "33") (pinfunction "GPIO_!_33") (pintype "passive"))
      (node (ref "U1") (pin "82") (pinfunction "PL1_82") (pintype "bidirectional"))
    )
    (net (code "60") (name "/PL2") (class "Default")
      (node (ref "J10") (pin "47") (pinfunction "47_47") (pintype "passive"))
      (node (ref "J2/J4") (pin "32") (pinfunction "GPIO_!_32") (pintype "passive"))
      (node (ref "U1") (pin "83") (pinfunction "PL2_83") (pintype "bidirectional"))
    )
    (net (code "61") (name "/PL3") (class "Default")
      (node (ref "J10") (pin "49") (pinfunction "49_49") (pintype "passive"))
      (node (ref "J2/J4") (pin "31") (pinfunction "GPIO_!_31") (pintype "passive"))
      (node (ref "U1") (pin "84") (pinfunction "PL3_84") (pintype "bidirectional"))
    )
    (net (code "62") (name "/PL4") (class "Default")
      (node (ref "J10") (pin "65") (pinfunction "65_65") (pintype "passive"))
      (node (ref "J2/J4") (pin "36") (pinfunction "Timer_Cap/GPIO_!_36") (pintype "passive"))
      (node (ref "U1") (pin "85") (pinfunction "PL4_85") (pintype "bidirectional"))
    )
    (net (code "63") (name "/PL5") (class "Default")
      (node (ref "J10") (pin "79") (pinfunction "79_79") (pintype "passive"))
      (node (ref "J2/J4") (pin "35") (pinfunction "Timer_Cap/GPIO_!_35") (pintype "passive"))
      (node (ref "U1") (pin "86") (pinfunction "PL5_86") (pintype "bidirectional"))
    )
    (net (code "64") (name "/PM0") (class "Default")
      (node (ref "J10") (pin "41") (pinfunction "41_41") (pintype "passive"))
      (node (ref "J6/J8") (pin "37") (pinfunction "PWM/GPIO_!_37") (pintype "passive"))
      (node (ref "U1") (pin "78") (pinfunction "PM0_78") (pintype "bidirectional"))
    )
    (net (code "65") (name "/PM1") (class "Default")
      (node (ref "J10") (pin "39") (pinfunction "39_39") (pintype "passive"))
      (node (ref "J6/J8") (pin "36") (pinfunction "Timer_Cap/GPIO_!_36") (pintype "passive"))
      (node (ref "U1") (pin "77") (pinfunction "PM1_77") (pintype "bidirectional"))
    )
    (net (code "66") (name "/PM2") (class "Default")
      (node (ref "J10") (pin "37") (pinfunction "37_37") (pintype "passive"))
      (node (ref "J6/J8") (pin "35") (pinfunction "Timer_Cap/GPIO_!_35") (pintype "passive"))
      (node (ref "U1") (pin "76") (pinfunction "PM2_76") (pintype "bidirectional"))
    )
    (net (code "67") (name "/PM3") (class "Default")
      (node (ref "J10") (pin "33") (pinfunction "33_33") (pintype "passive"))
      (node (ref "J2/J4") (pin "19") (pinfunction "PWM/GPIO_!_19") (pintype "passive"))
      (node (ref "U1") (pin "75") (pinfunction "PM3_75") (pintype "bidirectional"))
    )
    (net (code "68") (name "/PM4") (class "Default")
      (node (ref "J1/J3") (pin "29") (pinfunction "Analog_Out/I2S_SDout_29") (pintype "passive"))
      (node (ref "J10") (pin "92") (pinfunction "92_92") (pintype "passive"))
      (node (ref "U1") (pin "74") (pinfunction "PM4_74") (pintype "bidirectional"))
    )
    (net (code "69") (name "/PM5") (class "Default")
      (node (ref "J1/J3") (pin "30") (pinfunction "Analog_Out/I2S_SDin_30") (pintype "passive"))
      (node (ref "J10") (pin "90") (pinfunction "90_90") (pintype "passive"))
      (node (ref "U1") (pin "73") (pinfunction "PM5_73") (pintype "bidirectional"))
    )
    (net (code "70") (name "/PM6") (class "Default")
      (node (ref "J10") (pin "88") (pinfunction "88_88") (pintype "passive"))
      (node (ref "J6/J8") (pin "11") (pinfunction "GPIO_!_11") (pintype "passive"))
      (node (ref "U1") (pin "72") (pinfunction "PM6_72") (pintype "bidirectional"))
    )
    (net (code "71") (name "/PM7") (class "Default")
      (node (ref "J10") (pin "86") (pinfunction "86_86") (pintype "passive"))
      (node (ref "J6/J8") (pin "19") (pinfunction "PWM/GPIO_!_19") (pintype "passive"))
      (node (ref "U1") (pin "71") (pinfunction "PM7_71") (pintype "bidirectional"))
    )
    (net (code "72") (name "/PN0") (class "Default")
      (node (ref "D2") (pin "1") (pinfunction "A_1") (pintype "passive"))
      (node (ref "J10") (pin "85") (pinfunction "85_85") (pintype "passive"))
      (node (ref "U1") (pin "107") (pinfunction "PN0_107") (pintype "bidirectional"))
    )
    (net (code "73") (name "/PN1") (class "Default")
      (node (ref "D1") (pin "1") (pinfunction "A_1") (pintype "passive"))
      (node (ref "J10") (pin "87") (pinfunction "87_87") (pintype "passive"))
      (node (ref "U1") (pin "108") (pinfunction "PN1_108") (pintype "bidirectional"))
    )
    (net (code "74") (name "/PN2") (class "Default")
      (node (ref "J10") (pin "89") (pinfunction "89_89") (pintype "passive"))
      (node (ref "J2/J4") (pin "13") (pinfunction "SPI_CS/GPIO_!_13") (pintype "passive"))
      (node (ref "U1") (pin "109") (pinfunction "PN2_109") (pintype "bidirectional"))
    )
    (net (code "75") (name "/PN3") (class "Default")
      (node (ref "J10") (pin "91") (pinfunction "91_91") (pintype "passive"))
      (node (ref "J2/J4") (pin "12") (pinfunction "SPI_CS/GPIO_!_12") (pintype "passive"))
      (node (ref "U1") (pin "110") (pinfunction "PN3_110") (pintype "bidirectional"))
    )
    (net (code "76") (name "/PN4") (class "Default")
      (node (ref "J10") (pin "81") (pinfunction "81_81") (pintype "passive"))
      (node (ref "J5/J7") (pin "10") (pinfunction "I2C_SDA_10") (pintype "passive"))
      (node (ref "U1") (pin "111") (pinfunction "PN4_111") (pintype "bidirectional"))
    )
    (net (code "77") (name "/PN5") (class "Default")
      (node (ref "J10") (pin "83") (pinfunction "83_83") (pintype "passive"))
      (node (ref "J5/J7") (pin "9") (pinfunction "I2C_SCL_9") (pintype "passive"))
      (node (ref "U1") (pin "112") (pinfunction "PN5_112") (pintype "bidirectional"))
    )
    (net (code "78") (name "/PP0") (class "Default")
      (node (ref "J10") (pin "54") (pinfunction "54_54") (pintype "passive"))
      (node (ref "J5/J7") (pin "3") (pinfunction "LP_UART_RX_3") (pintype "passive"))
      (node (ref "U1") (pin "118") (pinfunction "PP0_118") (pintype "bidirectional"))
    )
    (net (code "79") (name "/PP1") (class "Default")
      (node (ref "J10") (pin "56") (pinfunction "56_56") (pintype "passive"))
      (node (ref "J5/J7") (pin "4") (pinfunction "LP_UART_TX_4") (pintype "passive"))
      (node (ref "U1") (pin "119") (pinfunction "PP1_119") (pintype "bidirectional"))
    )
    (net (code "80") (name "/PP2") (class "Default")
      (node (ref "J10") (pin "71") (pinfunction "71_71") (pintype "passive"))
      (node (ref "J2/J4") (pin "11") (pinfunction "GPIO_!_11") (pintype "passive"))
      (node (ref "U1") (pin "103") (pinfunction "PP2_103") (pintype "bidirectional"))
    )
    (net (code "81") (name "/PP3") (class "Default")
      (node (ref "J10") (pin "73") (pinfunction "73_73") (pintype "passive"))
      (node (ref "J6/J8") (pin "13") (pinfunction "SPI_CS/GPIO_!_13") (pintype "passive"))
      (node (ref "U1") (pin "104") (pinfunction "PP3_104") (pintype "bidirectional"))
    )
    (net (code "82") (name "/PP4") (class "Default")
      (node (ref "J10") (pin "78") (pinfunction "78_78") (pintype "passive"))
      (node (ref "J5/J7") (pin "8") (pinfunction "GPIO_!_8") (pintype "passive"))
      (node (ref "U1") (pin "105") (pinfunction "PP4_105") (pintype "bidirectional"))
    )
    (net (code "83") (name "/PP5") (class "Default")
      (node (ref "J10") (pin "80") (pinfunction "80_80") (pintype "passive"))
      (node (ref "J6/J8") (pin "18") (pinfunction "GPIO_!_18") (pintype "passive"))
      (node (ref "U1") (pin "106") (pinfunction "PP5_106") (pintype "bidirectional"))
    )
    (net (code "84") (name "/PQ0") (class "Default")
      (node (ref "J10") (pin "51") (pinfunction "51_51") (pintype "passive"))
      (node (ref "J5/J7") (pin "7") (pinfunction "SPI_CLK_7") (pintype "passive"))
      (node (ref "U1") (pin "5") (pinfunction "PQ0_5") (pintype "bidirectional"))
    )
    (net (code "85") (name "/PQ1") (class "Default")
      (node (ref "J10") (pin "53") (pinfunction "53_53") (pintype "passive"))
      (node (ref "J6/J8") (pin "12") (pinfunction "SPI_CS/GPIO_!_12") (pintype "passive"))
      (node (ref "U1") (pin "6") (pinfunction "PQ1_6") (pintype "bidirectional"))
    )
    (net (code "86") (name "/PQ2") (class "Default")
      (node (ref "J10") (pin "55") (pinfunction "55_55") (pintype "passive"))
      (node (ref "J6/J8") (pin "15") (pinfunction "SPI_MOSI_15") (pintype "passive"))
      (node (ref "R19") (pin "1") (pinfunction "1_1") (pintype "passive"))
      (node (ref "U1") (pin "11") (pinfunction "PQ2_11") (pintype "bidirectional"))
    )
    (net (code "87") (name "/PQ3") (class "Default")
      (node (ref "J10") (pin "57") (pinfunction "57_57") (pintype "passive"))
      (node (ref "J6/J8") (pin "14") (pinfunction "SPI_MISO_14") (pintype "passive"))
      (node (ref "R20") (pin "1") (pinfunction "1_1") (pintype "passive"))
      (node (ref "U1") (pin "27") (pinfunction "PQ3_27") (pintype "bidirectional"))
    )
    (net (code "88") (name "/TARGET_ID") (class "Default")
      (node (ref "R18") (pin "2") (pinfunction "2_2") (pintype "passive"))
      (node (ref "TP7") (pin "1") (pintype "passive"))
      (node (ref "U2") (pin "2") (pinfunction "D-_2") (pintype "passive"))
      (node (ref "U7") (pin "4") (pinfunction "ID_4") (pintype "passive"))
    )
    (net (code "89") (name "/USBD_N") (class "Default")
      (node (ref "TP5") (pin "1") (pintype "passive"))
      (node (ref "U1") (pin "93") (pinfunction "PL7_93") (pintype "bidirectional"))
      (node (ref "U2") (pin "1") (pinfunction "D+_1") (pintype "passive"))
      (node (ref "U7") (pin "2") (pinfunction "D-_2") (pintype "passive"))
    )
    (net (code "90") (name "/USBD_P") (class "Default")
      (node (ref "TP6") (pin "1") (pintype "passive"))
      (node (ref "U1") (pin "94") (pinfunction "PL6_94") (pintype "bidirectional"))
      (node (ref "U2") (pin "3") (pinfunction "ID_3") (pintype "passive"))
      (node (ref "U7") (pin "3") (pinfunction "D+_3") (pintype "passive"))
    )
    (net (code "91") (name "GND") (class "Default")
      (node (ref "BSL") (pin "5") (pinfunction "5_5") (pintype "passive"))
      (node (ref "C23") (pin "1") (pinfunction "1_1") (pintype "passive"))
      (node (ref "C24") (pin "1") (pinfunction "1_1") (pintype "passive"))
      (node (ref "C25") (pin "1") (pinfunction "1_1") (pintype "passive"))
      (node (ref "C26") (pin "1") (pinfunction "1_1") (pintype "passive"))
      (node (ref "C27") (pin "1") (pinfunction "1_1") (pintype "passive"))
      (node (ref "C28") (pin "1") (pinfunction "1_1") (pintype "passive"))
      (node (ref "C29") (pin "1") (pinfunction "1_1") (pintype "passive"))
      (node (ref "C30") (pin "1") (pinfunction "1_1") (pintype "passive"))
      (node (ref "C32") (pin "2") (pinfunction "2_2") (pintype "passive"))
      (node (ref "J1/J3") (pin "22") (pinfunction "GND_22") (pintype "power_in"))
      (node (ref "J10") (pin "3") (pinfunction "3_3") (pintype "passive"))
      (node (ref "J10") (pin "35") (pinfunction "35_35") (pintype "passive"))
      (node (ref "J10") (pin "36") (pinfunction "36_36") (pintype "passive"))
      (node (ref "J10") (pin "4") (pinfunction "4_4") (pintype "passive"))
      (node (ref "J10") (pin "61") (pinfunction "61_61") (pintype "passive"))
      (node (ref "J10") (pin "62") (pinfunction "62_62") (pintype "passive"))
      (node (ref "J10") (pin "96") (pinfunction "96_96") (pintype "passive"))
      (node (ref "J2/J4") (pin "20") (pinfunction "GND_20") (pintype "power_in"))
      (node (ref "J5/J7") (pin "22") (pinfunction "GND_22") (pintype "power_in"))
      (node (ref "J6/J8") (pin "20") (pinfunction "GND_20") (pintype "power_in"))
      (node (ref "R27") (pin "1") (pinfunction "1_1") (pintype "passive"))
      (node (ref "R33") (pin "1") (pinfunction "1_1") (pintype "passive"))
      (node (ref "R52") (pin "1") (pinfunction "1_1") (pintype "passive"))
      (node (ref "TP14") (pin "1") (pintype "passive"))
      (node (ref "TP15") (pin "1") (pintype "passive"))
      (node (ref "TP16") (pin "1") (pintype "passive"))
      (node (ref "TP17") (pin "1") (pintype "passive"))
      (node (ref "U2") (pin "4") (pinfunction "GND_4") (pintype "power_in"))
      (node (ref "U7") (pin "5") (pinfunction "GND_5") (pintype "passive"))
      (node (ref "USR_SW1") (pin "1") (pinfunction "1_1") (pintype "passive"))
      (node (ref "USR_SW1") (pin "2") (pinfunction "2_2") (pintype "passive"))
      (node (ref "USR_SW1") (pin "3") (pinfunction "3_3") (pintype "passive"))
      (node (ref "USR_SW2") (pin "1") (pinfunction "1_1") (pintype "passive"))
      (node (ref "USR_SW2") (pin "2") (pinfunction "2_2") (pintype "passive"))
      (node (ref "USR_SW2") (pin "3") (pinfunction "3_3") (pintype "passive"))
    )
    (net (code "92") (name "MCU_3V3") (class "Default")
      (node (ref "R1") (pin "2") (pinfunction "2_2") (pintype "passive"))
      (node (ref "R2") (pin "2") (pinfunction "2_2") (pintype "passive"))
    )
    (net (code "93") (name "Net-(BSL-Pad6)") (class "Default")
      (node (ref "BSL") (pin "6") (pinfunction "6_6") (pintype "passive"))
      (node (ref "R4") (pin "1") (pinfunction "1_1") (pintype "passive"))
    )
    (net (code "94") (name "Net-(BSL-Pad8)") (class "Default")
      (node (ref "BSL") (pin "8") (pinfunction "8_8") (pintype "passive"))
      (node (ref "R3") (pin "1") (pinfunction "1_1") (pintype "passive"))
    )
    (net (code "95") (name "Net-(C32-Pad1)") (class "Default")
      (node (ref "C32") (pin "1") (pinfunction "1_1") (pintype "passive"))
      (node (ref "R52") (pin "2") (pinfunction "2_2") (pintype "passive"))
      (node (ref "U7") (pin "10") (pinfunction "10_10") (pintype "passive"))
      (node (ref "U7") (pin "11") (pinfunction "11_11") (pintype "passive"))
      (node (ref "U7") (pin "6") (pinfunction "6_6") (pintype "passive"))
      (node (ref "U7") (pin "7") (pinfunction "7_7") (pintype "passive"))
      (node (ref "U7") (pin "8") (pinfunction "8_8") (pintype "passive"))
      (node (ref "U7") (pin "9") (pinfunction "9_9") (pintype "passive"))
    )
    (net (code "96") (name "Net-(D1-K)") (class "Default")
      (node (ref "D1") (pin "2") (pinfunction "K_2") (pintype "passive"))
      (node (ref "R33") (pin "2") (pinfunction "2_2") (pintype "passive"))
    )
    (net (code "97") (name "Net-(D2-K)") (class "Default")
      (node (ref "D2") (pin "2") (pinfunction "K_2") (pintype "passive"))
      (node (ref "R27") (pin "2") (pinfunction "2_2") (pintype "passive"))
    )
    (net (code "98") (name "PD6") (class "Default")
      (node (ref "J1/J3") (pin "28") (pinfunction "Analog_In/I2S_SCLK_28") (pintype "passive"))
      (node (ref "J10") (pin "44") (pinfunction "44_44") (pintype "passive"))
      (node (ref "U1") (pin "127") (pinfunction "PD6_127") (pintype "bidirectional"))
    )
    (net (code "99") (name "PF0") (class "Default")
      (node (ref "J10") (pin "66") (pinfunction "66_66") (pintype "passive"))
      (node (ref "U1") (pin "42") (pinfunction "PF0_42") (pintype "bidirectional"))
    )
    (net (code "100") (name "PF4") (class "Default")
      (node (ref "J10") (pin "64") (pinfunction "64_64") (pintype "passive"))
      (node (ref "U1") (pin "46") (pinfunction "PF4_46") (pintype "bidirectional"))
    )
    (net (code "101") (name "PQ4") (class "Default")
      (node (ref "J10") (pin "93") (pinfunction "93_93") (pintype "passive"))
      (node (ref "U1") (pin "102") (pinfunction "PQ4_102") (pintype "bidirectional"))
    )
    (net (code "102") (name "TARGET_RXD") (class "Default")
      (node (ref "JP4") (pin "1") (pinfunction "1_1") (pintype "passive"))
    )
    (net (code "103") (name "TARGET_TXD") (class "Default")
      (node (ref "JP5") (pin "1") (pinfunction "1_1") (pintype "passive"))
    )
    (net (code "104") (name "TARGET_VBUS") (class "Default")
      (node (ref "J10") (pin "60") (pinfunction "60_60") (pintype "passive"))
      (node (ref "TP4") (pin "1") (pintype "passive"))
      (node (ref "U1") (pin "96") (pinfunction "PB1_96") (pintype "bidirectional"))
      (node (ref "U2") (pin "6") (pinfunction "VBUS_6") (pintype "passive"))
      (node (ref "U7") (pin "1") (pinfunction "VBUS_1") (pintype "passive"))
    )
    (net (code "105") (name "TCK_SWDCLK") (class "Default")
      (node (ref "R1") (pin "1") (pinfunction "1_1") (pintype "passive"))
      (node (ref "U1") (pin "100") (pinfunction "PC0/TCK/SWCLK_100") (pintype "bidirectional"))
    )
    (net (code "106") (name "TDI") (class "Default")
      (node (ref "U1") (pin "98") (pinfunction "PC2/TDI_98") (pintype "bidirectional"))
    )
    (net (code "107") (name "TDO_SWO") (class "Default")
      (node (ref "U1") (pin "97") (pinfunction "PC3/TDO/SWO_97") (pintype "bidirectional"))
    )
    (net (code "108") (name "TGT_RST") (class "Default")
      (node (ref "BSL") (pin "4") (pinfunction "4_4") (pintype "passive"))
      (node (ref "J10") (pin "94") (pinfunction "94_94") (pintype "passive"))
      (node (ref "J2/J4") (pin "16") (pinfunction "RST_16") (pintype "passive"))
      (node (ref "J6/J8") (pin "16") (pinfunction "RST_16") (pintype "passive"))
    )
    (net (code "109") (name "TMS_SWDIO") (class "Default")
      (node (ref "R2") (pin "1") (pinfunction "1_1") (pintype "passive"))
      (node (ref "U1") (pin "99") (pinfunction "PC1/TMS/SWDIO_99") (pintype "bidirectional"))
    )
    (net (code "110") (name "VREF+") (class "Default")
      (node (ref "J10") (pin "34") (pinfunction "34_34") (pintype "passive"))
    )
    (net (code "111") (name "Wake") (class "Default")
      (node (ref "J10") (pin "95") (pinfunction "95_95") (pintype "passive"))
    )
    (net (code "112") (name "unconnected-(BSL-Pad2)") (class "Default")
      (node (ref "BSL") (pin "2") (pinfunction "2_2") (pintype "passive"))
    )
    (net (code "113") (name "unconnected-(BSL-Pad7)") (class "Default")
      (node (ref "BSL") (pin "7") (pinfunction "7_7") (pintype "passive"))
    )
    (net (code "114") (name "unconnected-(U2-NC-Pad5)") (class "Default")
      (node (ref "U2") (pin "5") (pinfunction "NC_5") (pintype "passive"))
    )
  )
)
